# FishingReelController.net
KiCad netlist of a schematic drawn in EAGLE
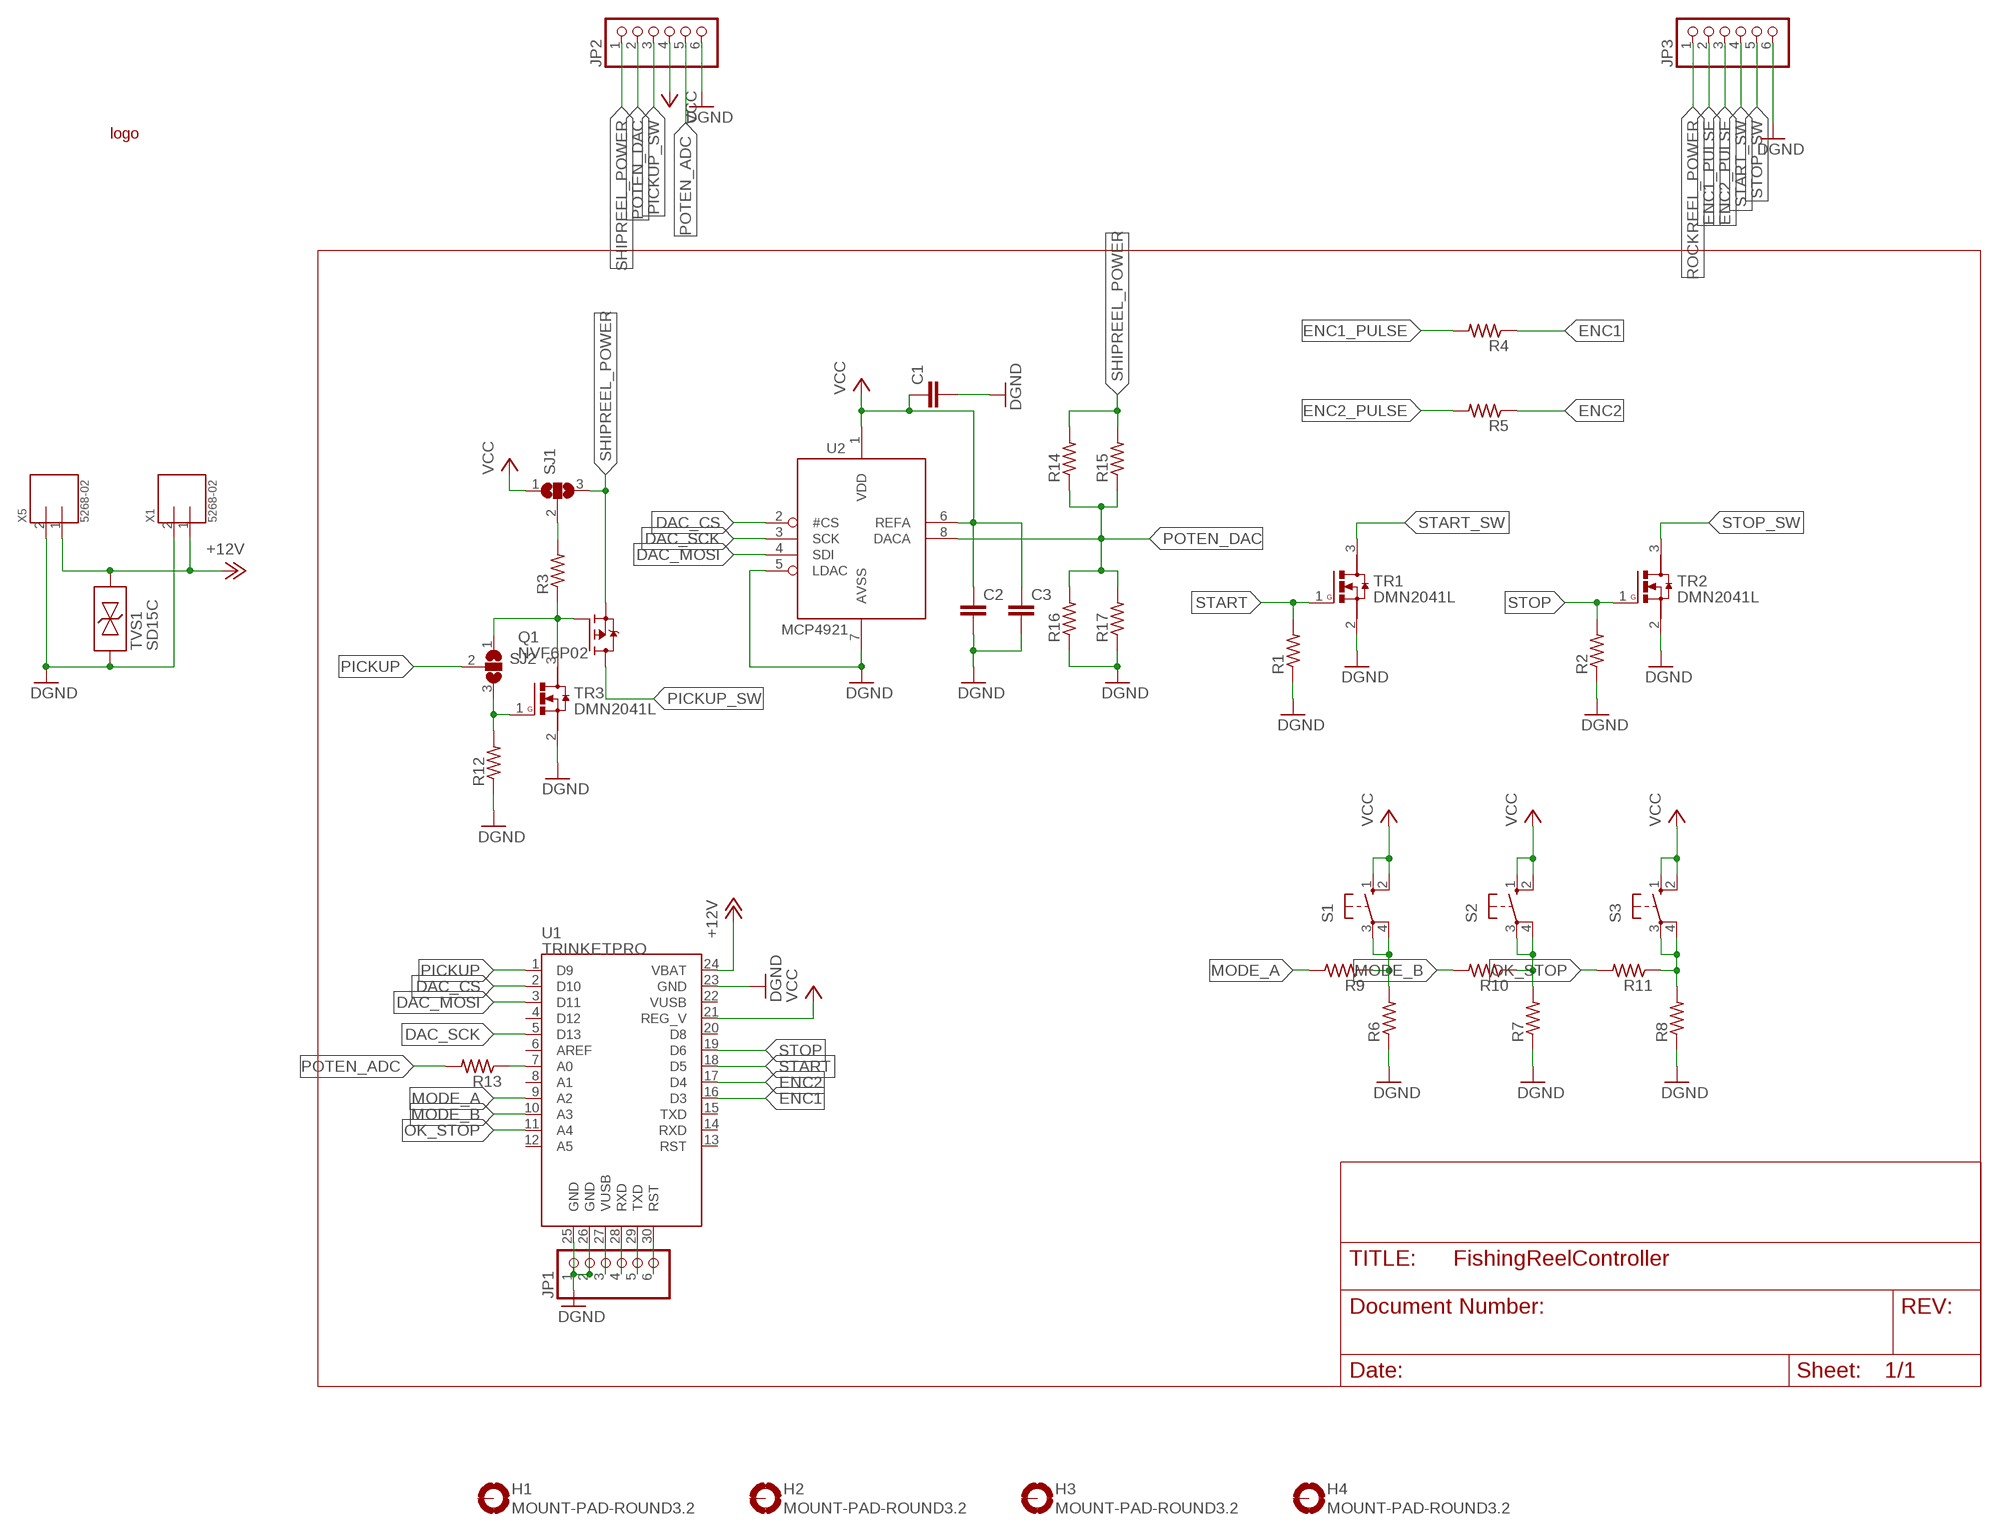
[diagram p0: schematic, sheet 1]

(export (version "E")
  (design (tool "Eeschema 10.0.6"))
  (components
    (comp (ref "C1")
      (value "C0603(1608)")
      (footprint "eagle-import:C0603(1608)")
      (libsource (lib "eagle-import") (part "C0603(1608)"))
    )
    (comp (ref "C2")
      (value "C0603(1608)")
      (footprint "eagle-import:C0603(1608)")
      (libsource (lib "eagle-import") (part "C0603(1608)"))
    )
    (comp (ref "C3")
      (value "C0603(1608)")
      (footprint "eagle-import:C0603(1608)")
      (libsource (lib "eagle-import") (part "C0603(1608)"))
    )
    (comp (ref "H1")
      (value "MOUNT-PAD-ROUND3.2")
      (footprint "eagle-import:3,2-PAD")
      (libsource (lib "eagle-import") (part "MOUNT-PAD-ROUND3.2"))
    )
    (comp (ref "H2")
      (value "MOUNT-PAD-ROUND3.2")
      (footprint "eagle-import:3,2-PAD")
      (libsource (lib "eagle-import") (part "MOUNT-PAD-ROUND3.2"))
    )
    (comp (ref "H3")
      (value "MOUNT-PAD-ROUND3.2")
      (footprint "eagle-import:3,2-PAD")
      (libsource (lib "eagle-import") (part "MOUNT-PAD-ROUND3.2"))
    )
    (comp (ref "H4")
      (value "MOUNT-PAD-ROUND3.2")
      (footprint "eagle-import:3,2-PAD")
      (libsource (lib "eagle-import") (part "MOUNT-PAD-ROUND3.2"))
    )
    (comp (ref "JP1")
      (value "PINHD-1X6CB")
      (footprint "eagle-import:1X06-CLEANBIG")
      (libsource (lib "eagle-import") (part "PINHD-1X6CB"))
    )
    (comp (ref "JP2")
      (value "PINHD-1X6CB")
      (footprint "eagle-import:1X06-CLEANBIG")
      (libsource (lib "eagle-import") (part "PINHD-1X6CB"))
    )
    (comp (ref "JP3")
      (value "PINHD-1X6CB")
      (footprint "eagle-import:1X06-CLEANBIG")
      (libsource (lib "eagle-import") (part "PINHD-1X6CB"))
    )
    (comp (ref "LOGO1")
      (value "GRADEFREELOGO-20")
      (footprint "eagle-import:GRADEFREELOGO-20")
      (libsource (lib "eagle-import") (part "GRADEFREELOGO-20"))
    )
    (comp (ref "Q1")
      (value "NVF6P02")
      (footprint "eagle-import:SOT223")
      (libsource (lib "eagle-import") (part "NVF6P02"))
    )
    (comp (ref "R1")
      (value "R0603(1608)")
      (footprint "eagle-import:R0603(1608)")
      (libsource (lib "eagle-import") (part "R0603(1608)"))
    )
    (comp (ref "R2")
      (value "R0603(1608)")
      (footprint "eagle-import:R0603(1608)")
      (libsource (lib "eagle-import") (part "R0603(1608)"))
    )
    (comp (ref "R3")
      (value "R0603(1608)")
      (footprint "eagle-import:R0603(1608)")
      (libsource (lib "eagle-import") (part "R0603(1608)"))
    )
    (comp (ref "R4")
      (value "R0603(1608)")
      (footprint "eagle-import:R0603(1608)")
      (libsource (lib "eagle-import") (part "R0603(1608)"))
    )
    (comp (ref "R5")
      (value "R0603(1608)")
      (footprint "eagle-import:R0603(1608)")
      (libsource (lib "eagle-import") (part "R0603(1608)"))
    )
    (comp (ref "R6")
      (value "R0603(1608)")
      (footprint "eagle-import:R0603(1608)")
      (libsource (lib "eagle-import") (part "R0603(1608)"))
    )
    (comp (ref "R7")
      (value "R0603(1608)")
      (footprint "eagle-import:R0603(1608)")
      (libsource (lib "eagle-import") (part "R0603(1608)"))
    )
    (comp (ref "R8")
      (value "R0603(1608)")
      (footprint "eagle-import:R0603(1608)")
      (libsource (lib "eagle-import") (part "R0603(1608)"))
    )
    (comp (ref "R9")
      (value "R0603(1608)")
      (footprint "eagle-import:R0603(1608)")
      (libsource (lib "eagle-import") (part "R0603(1608)"))
    )
    (comp (ref "R10")
      (value "R0603(1608)")
      (footprint "eagle-import:R0603(1608)")
      (libsource (lib "eagle-import") (part "R0603(1608)"))
    )
    (comp (ref "R11")
      (value "R0603(1608)")
      (footprint "eagle-import:R0603(1608)")
      (libsource (lib "eagle-import") (part "R0603(1608)"))
    )
    (comp (ref "R12")
      (value "R0603(1608)")
      (footprint "eagle-import:R0603(1608)")
      (libsource (lib "eagle-import") (part "R0603(1608)"))
    )
    (comp (ref "R13")
      (value "R0603(1608)")
      (footprint "eagle-import:R0603(1608)")
      (libsource (lib "eagle-import") (part "R0603(1608)"))
    )
    (comp (ref "R14")
      (value "R0603(1608)")
      (footprint "eagle-import:R0603(1608)")
      (libsource (lib "eagle-import") (part "R0603(1608)"))
    )
    (comp (ref "R15")
      (value "R0603(1608)")
      (footprint "eagle-import:R0603(1608)")
      (libsource (lib "eagle-import") (part "R0603(1608)"))
    )
    (comp (ref "R16")
      (value "R0603(1608)")
      (footprint "eagle-import:R0603(1608)")
      (libsource (lib "eagle-import") (part "R0603(1608)"))
    )
    (comp (ref "R17")
      (value "R0603(1608)")
      (footprint "eagle-import:R0603(1608)")
      (libsource (lib "eagle-import") (part "R0603(1608)"))
    )
    (comp (ref "S1")
      (value "40-XX")
      (footprint "eagle-import:B3F-40XX")
      (fields (field (name "MF") "OMRON COMPONENTS USA") (field (name "MPN") "B3F-4000"))
      (libsource (lib "eagle-import") (part "40-XX"))
    )
    (comp (ref "S2")
      (value "40-XX")
      (footprint "eagle-import:B3F-40XX")
      (fields (field (name "MF") "OMRON COMPONENTS USA") (field (name "MPN") "B3F-4000"))
      (libsource (lib "eagle-import") (part "40-XX"))
    )
    (comp (ref "S3")
      (value "40-XX")
      (footprint "eagle-import:B3F-40XX")
      (fields (field (name "MF") "OMRON COMPONENTS USA") (field (name "MPN") "B3F-4000"))
      (libsource (lib "eagle-import") (part "40-XX"))
    )
    (comp (ref "SJ1")
      (value "SJ2W")
      (footprint "eagle-import:SJ_2")
      (libsource (lib "eagle-import") (part "SJ2W"))
    )
    (comp (ref "SJ2")
      (value "SJ2W")
      (footprint "eagle-import:SJ_2")
      (libsource (lib "eagle-import") (part "SJ2W"))
    )
    (comp (ref "TR1")
      (value "DMN2041L")
      (footprint "eagle-import:SOT23")
      (libsource (lib "eagle-import") (part "DMN2041L"))
    )
    (comp (ref "TR2")
      (value "DMN2041L")
      (footprint "eagle-import:SOT23")
      (libsource (lib "eagle-import") (part "DMN2041L"))
    )
    (comp (ref "TR3")
      (value "DMN2041L")
      (footprint "eagle-import:SOT23")
      (libsource (lib "eagle-import") (part "DMN2041L"))
    )
    (comp (ref "TVS1")
      (value "SD15C")
      (footprint "eagle-import:SOD-323-NOPOL")
      (libsource (lib "eagle-import") (part "SD0"))
    )
    (comp (ref "U1")
      (value "TRINKETPRO")
      (footprint "eagle-import:TRINKETPRO")
      (libsource (lib "eagle-import") (part "TRINKETPRO"))
    )
    (comp (ref "U2")
      (value "MCP4921")
      (footprint "eagle-import:DIL08")
      (libsource (lib "eagle-import") (part "MCP4921"))
    )
    (comp (ref "X1")
      (value "5268-02")
      (footprint "eagle-import:5628-02")
      (libsource (lib "eagle-import") (part "5268-02"))
    )
    (comp (ref "X5")
      (value "5268-02")
      (footprint "eagle-import:5628-02")
      (libsource (lib "eagle-import") (part "5268-02"))
    )
  )
  (nets
    (net (code "1") (name "+12V") (class "Default")
      (node (ref "TVS1") (pin "2") (pinfunction "P$2_2") (pintype "bidirectional"))
      (node (ref "U1") (pin "24") (pinfunction "VBAT_24") (pintype "bidirectional"))
      (node (ref "X1") (pin "1") (pinfunction "1_1") (pintype "bidirectional"))
      (node (ref "X5") (pin "1") (pinfunction "1_1") (pintype "bidirectional"))
    )
    (net (code "2") (name "DAC_CS") (class "Default")
      (node (ref "U1") (pin "2") (pinfunction "D10_2") (pintype "bidirectional"))
      (node (ref "U2") (pin "2") (pinfunction "#CS_2") (pintype "input"))
    )
    (net (code "3") (name "DAC_MOSI") (class "Default")
      (node (ref "U1") (pin "3") (pinfunction "D11_3") (pintype "bidirectional"))
      (node (ref "U2") (pin "4") (pinfunction "SDI_4") (pintype "input"))
    )
    (net (code "4") (name "DAC_SCK") (class "Default")
      (node (ref "U1") (pin "5") (pinfunction "D13_5") (pintype "bidirectional"))
      (node (ref "U2") (pin "3") (pinfunction "SCK_3") (pintype "input"))
    )
    (net (code "5") (name "DGND") (class "Default")
      (node (ref "C1") (pin "2") (pinfunction "2_2") (pintype "passive"))
      (node (ref "C2") (pin "2") (pinfunction "2_2") (pintype "passive"))
      (node (ref "C3") (pin "2") (pinfunction "2_2") (pintype "passive"))
      (node (ref "JP1") (pin "1") (pinfunction "1_1") (pintype "passive"))
      (node (ref "JP1") (pin "2") (pinfunction "2_2") (pintype "passive"))
      (node (ref "JP2") (pin "6") (pinfunction "6_6") (pintype "passive"))
      (node (ref "JP3") (pin "6") (pinfunction "6_6") (pintype "passive"))
      (node (ref "R1") (pin "1") (pinfunction "1_1") (pintype "passive"))
      (node (ref "R12") (pin "1") (pinfunction "1_1") (pintype "passive"))
      (node (ref "R16") (pin "1") (pinfunction "1_1") (pintype "passive"))
      (node (ref "R17") (pin "1") (pinfunction "1_1") (pintype "passive"))
      (node (ref "R2") (pin "1") (pinfunction "1_1") (pintype "passive"))
      (node (ref "R6") (pin "1") (pinfunction "1_1") (pintype "passive"))
      (node (ref "R7") (pin "1") (pinfunction "1_1") (pintype "passive"))
      (node (ref "R8") (pin "1") (pinfunction "1_1") (pintype "passive"))
      (node (ref "TR1") (pin "2") (pinfunction "S_2") (pintype "bidirectional"))
      (node (ref "TR2") (pin "2") (pinfunction "S_2") (pintype "bidirectional"))
      (node (ref "TR3") (pin "2") (pinfunction "S_2") (pintype "bidirectional"))
      (node (ref "TVS1") (pin "1") (pinfunction "P$1_1") (pintype "bidirectional"))
      (node (ref "U1") (pin "23") (pinfunction "GND_23") (pintype "bidirectional"))
      (node (ref "U1") (pin "25") (pinfunction "GND_25") (pintype "bidirectional"))
      (node (ref "U1") (pin "26") (pinfunction "GND_26") (pintype "bidirectional"))
      (node (ref "U2") (pin "5") (pinfunction "LDAC_5") (pintype "input"))
      (node (ref "U2") (pin "7") (pinfunction "AVSS_7") (pintype "power_in"))
      (node (ref "X1") (pin "2") (pinfunction "2_2") (pintype "bidirectional"))
      (node (ref "X5") (pin "2") (pinfunction "2_2") (pintype "bidirectional"))
    )
    (net (code "6") (name "ENC1") (class "Default")
      (node (ref "R4") (pin "1") (pinfunction "1_1") (pintype "passive"))
      (node (ref "U1") (pin "16") (pinfunction "D3_16") (pintype "bidirectional"))
    )
    (net (code "7") (name "ENC1_PULSE") (class "Default")
      (node (ref "JP3") (pin "2") (pinfunction "2_2") (pintype "passive"))
      (node (ref "R4") (pin "2") (pinfunction "2_2") (pintype "passive"))
    )
    (net (code "8") (name "ENC2") (class "Default")
      (node (ref "R5") (pin "1") (pinfunction "1_1") (pintype "passive"))
      (node (ref "U1") (pin "17") (pinfunction "D4_17") (pintype "bidirectional"))
    )
    (net (code "9") (name "ENC2_PULSE") (class "Default")
      (node (ref "JP3") (pin "3") (pinfunction "3_3") (pintype "passive"))
      (node (ref "R5") (pin "2") (pinfunction "2_2") (pintype "passive"))
    )
    (net (code "10") (name "MODE_A") (class "Default")
      (node (ref "R9") (pin "2") (pinfunction "2_2") (pintype "passive"))
      (node (ref "U1") (pin "9") (pinfunction "A2_9") (pintype "bidirectional"))
    )
    (net (code "11") (name "MODE_B") (class "Default")
      (node (ref "R10") (pin "2") (pinfunction "2_2") (pintype "passive"))
      (node (ref "U1") (pin "10") (pinfunction "A3_10") (pintype "bidirectional"))
    )
    (net (code "12") (name "Net-(JP1-Pad3)") (class "Default")
      (node (ref "JP1") (pin "3") (pinfunction "3_3") (pintype "passive"))
      (node (ref "U1") (pin "27") (pinfunction "VUSB_27") (pintype "bidirectional"))
    )
    (net (code "13") (name "Net-(JP1-Pad4)") (class "Default")
      (node (ref "JP1") (pin "4") (pinfunction "4_4") (pintype "passive"))
      (node (ref "U1") (pin "28") (pinfunction "RXD_28") (pintype "bidirectional"))
    )
    (net (code "14") (name "Net-(JP1-Pad5)") (class "Default")
      (node (ref "JP1") (pin "5") (pinfunction "5_5") (pintype "passive"))
      (node (ref "U1") (pin "29") (pinfunction "TXD_29") (pintype "bidirectional"))
    )
    (net (code "15") (name "Net-(JP1-Pad6)") (class "Default")
      (node (ref "JP1") (pin "6") (pinfunction "6_6") (pintype "passive"))
      (node (ref "U1") (pin "30") (pinfunction "RST_30") (pintype "bidirectional"))
    )
    (net (code "16") (name "Net-(Q1-G)") (class "Default")
      (node (ref "Q1") (pin "1") (pinfunction "G_1") (pintype "passive"))
      (node (ref "R3") (pin "1") (pinfunction "1_1") (pintype "passive"))
      (node (ref "SJ2") (pin "1") (pinfunction "1_1") (pintype "passive"))
      (node (ref "TR3") (pin "3") (pinfunction "D_3") (pintype "bidirectional"))
    )
    (net (code "17") (name "Net-(R3-Pad2)") (class "Default")
      (node (ref "R3") (pin "2") (pinfunction "2_2") (pintype "passive"))
      (node (ref "SJ1") (pin "2") (pinfunction "2_2") (pintype "passive"))
    )
    (net (code "18") (name "Net-(S1-P)") (class "Default")
      (node (ref "R6") (pin "2") (pinfunction "2_2") (pintype "passive"))
      (node (ref "R9") (pin "1") (pinfunction "1_1") (pintype "passive"))
      (node (ref "S1") (pin "3") (pinfunction "P_3") (pintype "passive"))
      (node (ref "S1") (pin "4") (pinfunction "P1_4") (pintype "passive"))
    )
    (net (code "19") (name "Net-(S2-P)") (class "Default")
      (node (ref "R10") (pin "1") (pinfunction "1_1") (pintype "passive"))
      (node (ref "R7") (pin "2") (pinfunction "2_2") (pintype "passive"))
      (node (ref "S2") (pin "3") (pinfunction "P_3") (pintype "passive"))
      (node (ref "S2") (pin "4") (pinfunction "P1_4") (pintype "passive"))
    )
    (net (code "20") (name "Net-(S3-P)") (class "Default")
      (node (ref "R11") (pin "1") (pinfunction "1_1") (pintype "passive"))
      (node (ref "R8") (pin "2") (pinfunction "2_2") (pintype "passive"))
      (node (ref "S3") (pin "3") (pinfunction "P_3") (pintype "passive"))
      (node (ref "S3") (pin "4") (pinfunction "P1_4") (pintype "passive"))
    )
    (net (code "21") (name "Net-(TR3-G)") (class "Default")
      (node (ref "R12") (pin "2") (pinfunction "2_2") (pintype "passive"))
      (node (ref "SJ2") (pin "3") (pinfunction "3_3") (pintype "passive"))
      (node (ref "TR3") (pin "1") (pinfunction "G_1") (pintype "bidirectional"))
    )
    (net (code "22") (name "Net-(U1-A0)") (class "Default")
      (node (ref "R13") (pin "1") (pinfunction "1_1") (pintype "passive"))
      (node (ref "U1") (pin "7") (pinfunction "A0_7") (pintype "bidirectional"))
    )
    (net (code "23") (name "OK_STOP") (class "Default")
      (node (ref "R11") (pin "2") (pinfunction "2_2") (pintype "passive"))
      (node (ref "U1") (pin "11") (pinfunction "A4_11") (pintype "bidirectional"))
    )
    (net (code "24") (name "PICKUP") (class "Default")
      (node (ref "SJ2") (pin "2") (pinfunction "2_2") (pintype "passive"))
      (node (ref "U1") (pin "1") (pinfunction "D9_1") (pintype "bidirectional"))
    )
    (net (code "25") (name "PICKUP_SW") (class "Default")
      (node (ref "JP2") (pin "3") (pinfunction "3_3") (pintype "passive"))
      (node (ref "Q1") (pin "2") (pinfunction "D_2") (pintype "passive"))
      (node (ref "Q1") (pin "4") (pinfunction "D_4") (pintype "passive"))
    )
    (net (code "26") (name "POTEN_ADC") (class "Default")
      (node (ref "JP2") (pin "5") (pinfunction "5_5") (pintype "passive"))
      (node (ref "R13") (pin "2") (pinfunction "2_2") (pintype "passive"))
    )
    (net (code "27") (name "POTEN_DAC") (class "Default")
      (node (ref "JP2") (pin "2") (pinfunction "2_2") (pintype "passive"))
      (node (ref "R14") (pin "1") (pinfunction "1_1") (pintype "passive"))
      (node (ref "R15") (pin "1") (pinfunction "1_1") (pintype "passive"))
      (node (ref "R16") (pin "2") (pinfunction "2_2") (pintype "passive"))
      (node (ref "R17") (pin "2") (pinfunction "2_2") (pintype "passive"))
      (node (ref "U2") (pin "8") (pinfunction "DACA_8") (pintype "output"))
    )
    (net (code "28") (name "ROCKREEL_POWER") (class "Default")
      (node (ref "JP3") (pin "1") (pinfunction "1_1") (pintype "passive"))
    )
    (net (code "29") (name "SHIPREEL_POWER") (class "Default")
      (node (ref "JP2") (pin "1") (pinfunction "1_1") (pintype "passive"))
      (node (ref "Q1") (pin "3") (pinfunction "S_3") (pintype "passive"))
      (node (ref "R14") (pin "2") (pinfunction "2_2") (pintype "passive"))
      (node (ref "R15") (pin "2") (pinfunction "2_2") (pintype "passive"))
      (node (ref "SJ1") (pin "3") (pinfunction "3_3") (pintype "passive"))
    )
    (net (code "30") (name "START") (class "Default")
      (node (ref "R1") (pin "2") (pinfunction "2_2") (pintype "passive"))
      (node (ref "TR1") (pin "1") (pinfunction "G_1") (pintype "bidirectional"))
      (node (ref "U1") (pin "18") (pinfunction "D5_18") (pintype "bidirectional"))
    )
    (net (code "31") (name "START_SW") (class "Default")
      (node (ref "JP3") (pin "4") (pinfunction "4_4") (pintype "passive"))
      (node (ref "TR1") (pin "3") (pinfunction "D_3") (pintype "bidirectional"))
    )
    (net (code "32") (name "STOP") (class "Default")
      (node (ref "R2") (pin "2") (pinfunction "2_2") (pintype "passive"))
      (node (ref "TR2") (pin "1") (pinfunction "G_1") (pintype "bidirectional"))
      (node (ref "U1") (pin "19") (pinfunction "D6_19") (pintype "bidirectional"))
    )
    (net (code "33") (name "STOP_SW") (class "Default")
      (node (ref "JP3") (pin "5") (pinfunction "5_5") (pintype "passive"))
      (node (ref "TR2") (pin "3") (pinfunction "D_3") (pintype "bidirectional"))
    )
    (net (code "34") (name "VCC") (class "Default")
      (node (ref "C1") (pin "1") (pinfunction "1_1") (pintype "passive"))
      (node (ref "C2") (pin "1") (pinfunction "1_1") (pintype "passive"))
      (node (ref "C3") (pin "1") (pinfunction "1_1") (pintype "passive"))
      (node (ref "JP2") (pin "4") (pinfunction "4_4") (pintype "passive"))
      (node (ref "S1") (pin "1") (pinfunction "S_1") (pintype "passive"))
      (node (ref "S1") (pin "2") (pinfunction "S1_2") (pintype "passive"))
      (node (ref "S2") (pin "1") (pinfunction "S_1") (pintype "passive"))
      (node (ref "S2") (pin "2") (pinfunction "S1_2") (pintype "passive"))
      (node (ref "S3") (pin "1") (pinfunction "S_1") (pintype "passive"))
      (node (ref "S3") (pin "2") (pinfunction "S1_2") (pintype "passive"))
      (node (ref "SJ1") (pin "1") (pinfunction "1_1") (pintype "passive"))
      (node (ref "U1") (pin "21") (pinfunction "REG_V_21") (pintype "bidirectional"))
      (node (ref "U2") (pin "1") (pinfunction "VDD_1") (pintype "power_in"))
      (node (ref "U2") (pin "6") (pinfunction "REFA_6") (pintype "input"))
    )
    (net (code "35") (name "unconnected-(H1-MOUNT-PadB3,2)") (class "Default")
      (node (ref "H1") (pin "B3,2") (pinfunction "MOUNT_B3,2") (pintype "passive"))
    )
    (net (code "36") (name "unconnected-(H2-MOUNT-PadB3,2)") (class "Default")
      (node (ref "H2") (pin "B3,2") (pinfunction "MOUNT_B3,2") (pintype "passive"))
    )
    (net (code "37") (name "unconnected-(H3-MOUNT-PadB3,2)") (class "Default")
      (node (ref "H3") (pin "B3,2") (pinfunction "MOUNT_B3,2") (pintype "passive"))
    )
    (net (code "38") (name "unconnected-(H4-MOUNT-PadB3,2)") (class "Default")
      (node (ref "H4") (pin "B3,2") (pinfunction "MOUNT_B3,2") (pintype "passive"))
    )
    (net (code "39") (name "unconnected-(U1-A1-Pad8)") (class "Default")
      (node (ref "U1") (pin "8") (pinfunction "A1_8") (pintype "bidirectional"))
    )
    (net (code "40") (name "unconnected-(U1-A5-Pad12)") (class "Default")
      (node (ref "U1") (pin "12") (pinfunction "A5_12") (pintype "bidirectional"))
    )
    (net (code "41") (name "unconnected-(U1-AREF-Pad6)") (class "Default")
      (node (ref "U1") (pin "6") (pinfunction "AREF_6") (pintype "bidirectional"))
    )
    (net (code "42") (name "unconnected-(U1-D8-Pad20)") (class "Default")
      (node (ref "U1") (pin "20") (pinfunction "D8_20") (pintype "bidirectional"))
    )
    (net (code "43") (name "unconnected-(U1-D12-Pad4)") (class "Default")
      (node (ref "U1") (pin "4") (pinfunction "D12_4") (pintype "bidirectional"))
    )
    (net (code "44") (name "unconnected-(U1-RST-Pad13)") (class "Default")
      (node (ref "U1") (pin "13") (pinfunction "RST_13") (pintype "bidirectional"))
    )
    (net (code "45") (name "unconnected-(U1-RXD-Pad14)") (class "Default")
      (node (ref "U1") (pin "14") (pinfunction "RXD_14") (pintype "bidirectional"))
    )
    (net (code "46") (name "unconnected-(U1-TXD-Pad15)") (class "Default")
      (node (ref "U1") (pin "15") (pinfunction "TXD_15") (pintype "bidirectional"))
    )
    (net (code "47") (name "unconnected-(U1-VUSB-Pad22)") (class "Default")
      (node (ref "U1") (pin "22") (pinfunction "VUSB_22") (pintype "bidirectional"))
    )
  )
)
